# W707F.net
KiCad netlist of a schematic drawn in EAGLE
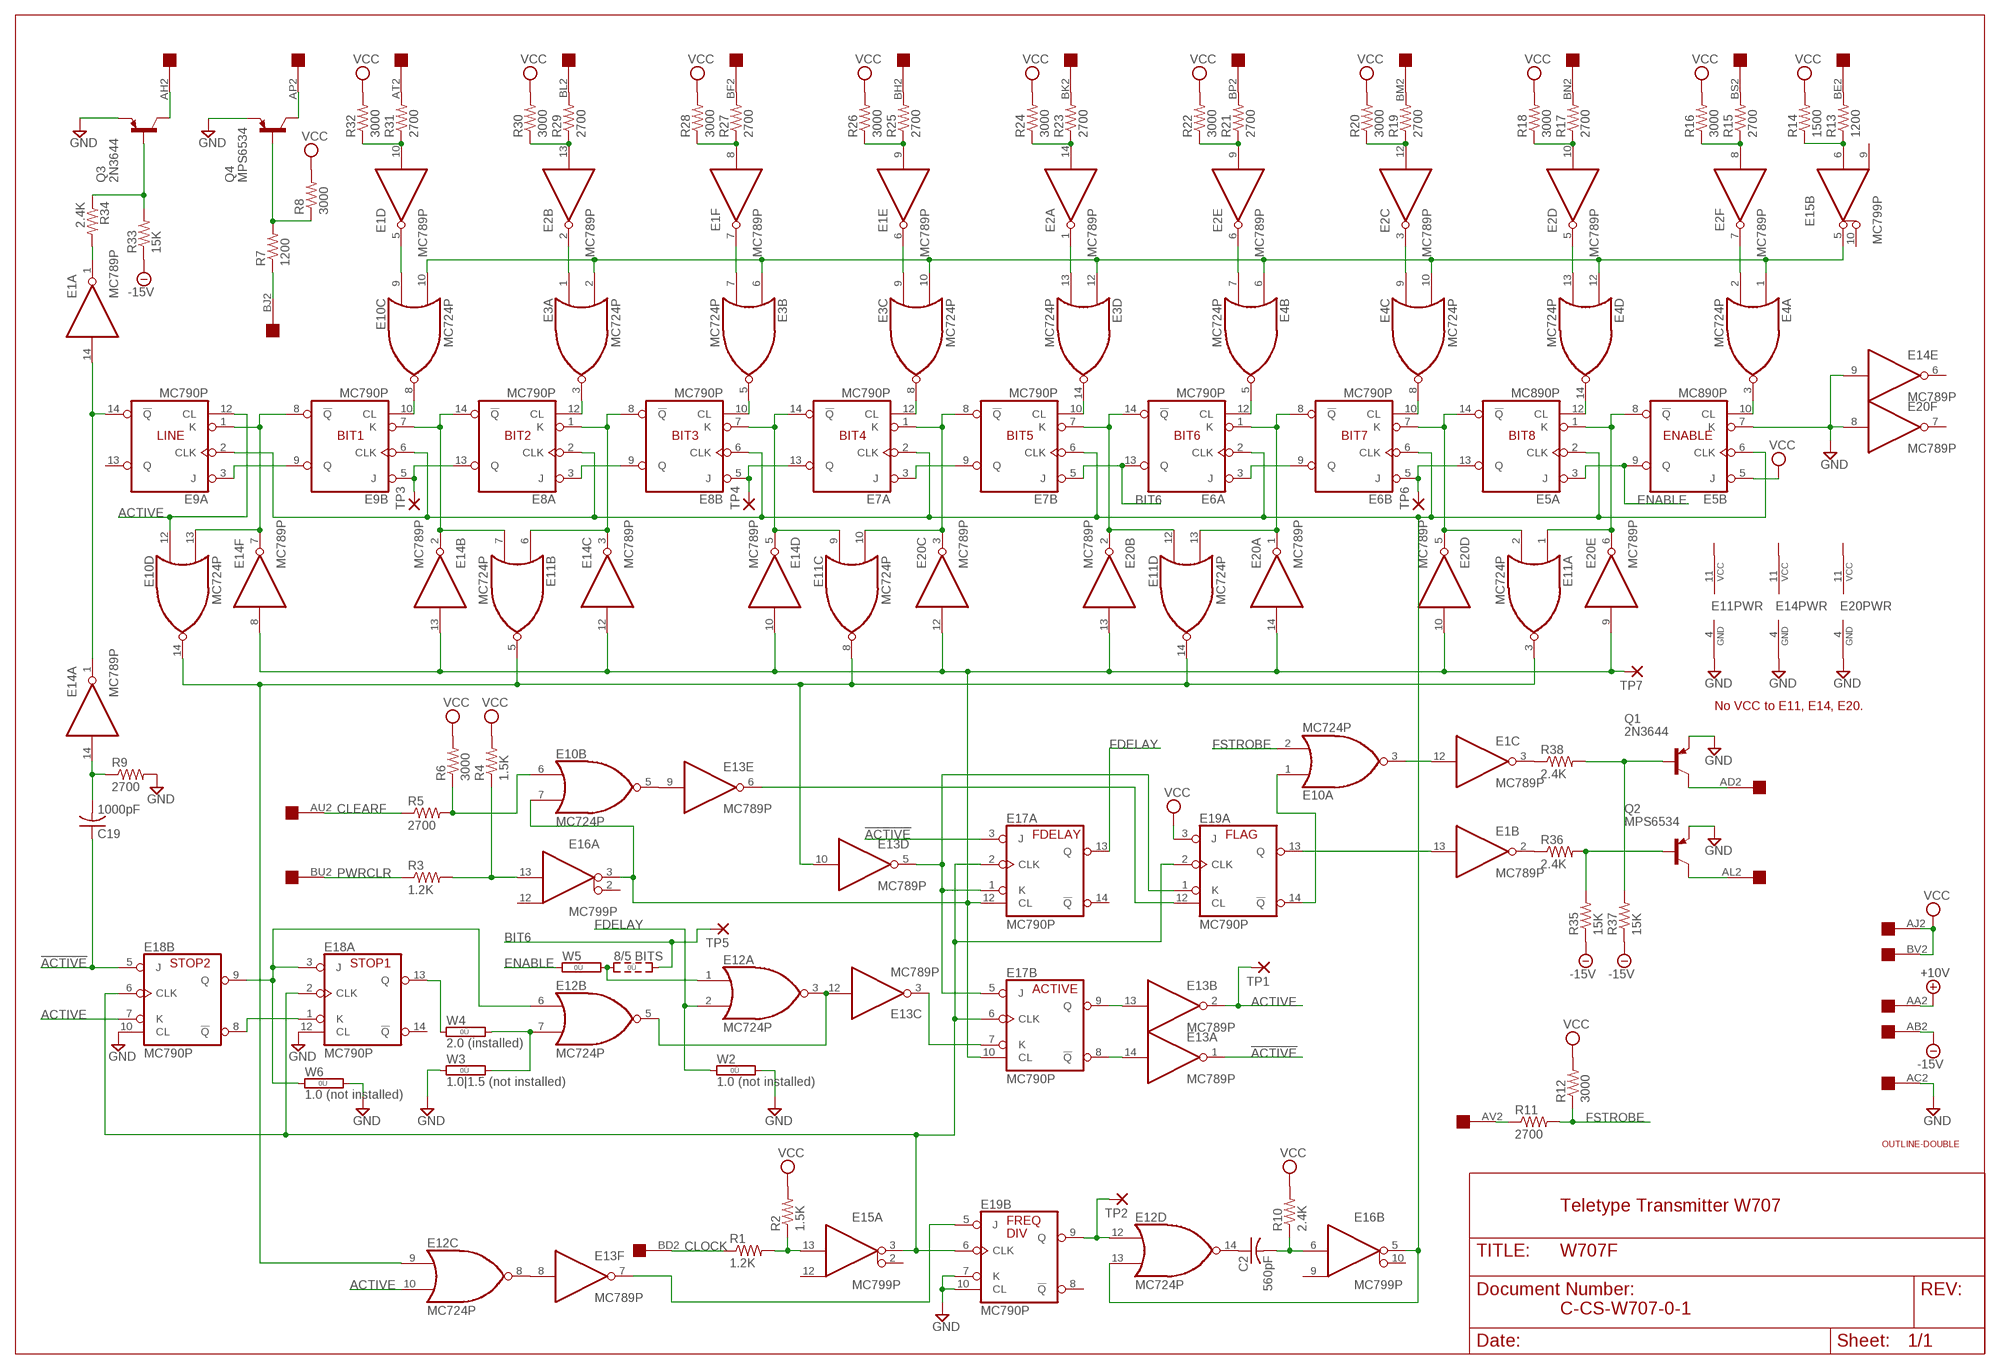
[diagram p0: schematic, sheet 1]

(export (version "E")
  (design (tool "Eeschema 10.0.6"))
  (components
    (comp (ref "C2")
      (value "560pF")
      (footprint "eagle-import:C050-025X075")
      (libsource (lib "eagle-import") (part "C-US050-025X075"))
    )
    (comp (ref "C19")
      (value "1000pF")
      (footprint "eagle-import:C050-025X075")
      (libsource (lib "eagle-import") (part "C-US050-025X075"))
    )
    (comp (ref "E1")
      (value "MC789P")
      (footprint "eagle-import:DIL14")
      (libsource (lib "eagle-import") (part "MC889P"))
    )
    (comp (ref "E2")
      (value "MC789P")
      (footprint "eagle-import:DIL14")
      (libsource (lib "eagle-import") (part "MC889P"))
    )
    (comp (ref "E3")
      (value "MC724P")
      (footprint "eagle-import:DIL14")
      (libsource (lib "eagle-import") (part "MC824P"))
    )
    (comp (ref "E4")
      (value "MC724P")
      (footprint "eagle-import:DIL14")
      (libsource (lib "eagle-import") (part "MC824P"))
    )
    (comp (ref "E5")
      (value "MC890P")
      (footprint "eagle-import:DIL14")
      (libsource (lib "eagle-import") (part "MC890P"))
    )
    (comp (ref "E6")
      (value "MC790P")
      (footprint "eagle-import:DIL14")
      (libsource (lib "eagle-import") (part "MC890P"))
    )
    (comp (ref "E7")
      (value "MC790P")
      (footprint "eagle-import:DIL14")
      (libsource (lib "eagle-import") (part "MC890P"))
    )
    (comp (ref "E8")
      (value "MC790P")
      (footprint "eagle-import:DIL14")
      (libsource (lib "eagle-import") (part "MC890P"))
    )
    (comp (ref "E9")
      (value "MC790P")
      (footprint "eagle-import:DIL14")
      (libsource (lib "eagle-import") (part "MC890P"))
    )
    (comp (ref "E10")
      (value "MC724P")
      (footprint "eagle-import:DIL14")
      (libsource (lib "eagle-import") (part "MC824P"))
    )
    (comp (ref "E11")
      (value "MC724P")
      (footprint "eagle-import:DIL14")
      (libsource (lib "eagle-import") (part "MC824P"))
    )
    (comp (ref "E12")
      (value "MC724P")
      (footprint "eagle-import:DIL14")
      (libsource (lib "eagle-import") (part "MC824P"))
    )
    (comp (ref "E13")
      (value "MC789P")
      (footprint "eagle-import:DIL14")
      (libsource (lib "eagle-import") (part "MC889P"))
    )
    (comp (ref "E14")
      (value "MC789P")
      (footprint "eagle-import:DIL14")
      (libsource (lib "eagle-import") (part "MC889P"))
    )
    (comp (ref "E15")
      (value "MC799P")
      (footprint "eagle-import:DIL14")
      (libsource (lib "eagle-import") (part "MC899P"))
    )
    (comp (ref "E16")
      (value "MC799P")
      (footprint "eagle-import:DIL14")
      (libsource (lib "eagle-import") (part "MC899P"))
    )
    (comp (ref "E17")
      (value "MC790P")
      (footprint "eagle-import:DIL14")
      (libsource (lib "eagle-import") (part "MC890P"))
    )
    (comp (ref "E18")
      (value "MC790P")
      (footprint "eagle-import:DIL14")
      (libsource (lib "eagle-import") (part "MC890P"))
    )
    (comp (ref "E19")
      (value "MC790P")
      (footprint "eagle-import:DIL14")
      (libsource (lib "eagle-import") (part "MC890P"))
    )
    (comp (ref "E20")
      (value "MC789P")
      (footprint "eagle-import:DIL14")
      (libsource (lib "eagle-import") (part "MC889P"))
    )
    (comp (ref "Q1")
      (value "2N3644")
      (footprint "eagle-import:TO39")
      (libsource (lib "eagle-import") (part "2N2904"))
    )
    (comp (ref "Q2")
      (value "MPS6534")
      (footprint "eagle-import:TO39")
      (libsource (lib "eagle-import") (part "2N2904"))
    )
    (comp (ref "Q3")
      (value "2N3644")
      (footprint "eagle-import:TO39")
      (libsource (lib "eagle-import") (part "2N2904"))
    )
    (comp (ref "Q4")
      (value "MPS6534")
      (footprint "eagle-import:TO39")
      (libsource (lib "eagle-import") (part "2N2904"))
    )
    (comp (ref "R1")
      (value "1.2K")
      (footprint "eagle-import:0207_10")
      (libsource (lib "eagle-import") (part "R-US_0207/10"))
    )
    (comp (ref "R2")
      (value "1.5K")
      (footprint "eagle-import:0207_10")
      (libsource (lib "eagle-import") (part "R-US_0207/10"))
    )
    (comp (ref "R3")
      (value "1.2K")
      (footprint "eagle-import:0207_10")
      (libsource (lib "eagle-import") (part "R-US_0207/10"))
    )
    (comp (ref "R4")
      (value "1.5K")
      (footprint "eagle-import:0207_10")
      (libsource (lib "eagle-import") (part "R-US_0207/10"))
    )
    (comp (ref "R5")
      (value "2700")
      (footprint "eagle-import:0207_10")
      (libsource (lib "eagle-import") (part "R-US_0207/10"))
    )
    (comp (ref "R6")
      (value "3000")
      (footprint "eagle-import:0207_10")
      (libsource (lib "eagle-import") (part "R-US_0207/10"))
    )
    (comp (ref "R7")
      (value "1200")
      (footprint "eagle-import:0207_10")
      (libsource (lib "eagle-import") (part "R-US_0207/10"))
    )
    (comp (ref "R8")
      (value "3000")
      (footprint "eagle-import:0207_10")
      (libsource (lib "eagle-import") (part "R-US_0207/10"))
    )
    (comp (ref "R9")
      (value "2700")
      (footprint "eagle-import:0207_10")
      (libsource (lib "eagle-import") (part "R-US_0207/10"))
    )
    (comp (ref "R10")
      (value "2.4K")
      (footprint "eagle-import:0207_10")
      (libsource (lib "eagle-import") (part "R-US_0207/10"))
    )
    (comp (ref "R11")
      (value "2700")
      (footprint "eagle-import:0207_10")
      (libsource (lib "eagle-import") (part "R-US_0207/10"))
    )
    (comp (ref "R12")
      (value "3000")
      (footprint "eagle-import:0207_10")
      (libsource (lib "eagle-import") (part "R-US_0207/10"))
    )
    (comp (ref "R13")
      (value "1200")
      (footprint "eagle-import:0207_10")
      (libsource (lib "eagle-import") (part "R-US_0207/10"))
    )
    (comp (ref "R14")
      (value "1500")
      (footprint "eagle-import:0207_10")
      (libsource (lib "eagle-import") (part "R-US_0207/10"))
    )
    (comp (ref "R15")
      (value "2700")
      (footprint "eagle-import:0207_10")
      (libsource (lib "eagle-import") (part "R-US_0207/10"))
    )
    (comp (ref "R16")
      (value "3000")
      (footprint "eagle-import:0207_10")
      (libsource (lib "eagle-import") (part "R-US_0207/10"))
    )
    (comp (ref "R17")
      (value "2700")
      (footprint "eagle-import:0207_10")
      (libsource (lib "eagle-import") (part "R-US_0207/10"))
    )
    (comp (ref "R18")
      (value "3000")
      (footprint "eagle-import:0207_10")
      (libsource (lib "eagle-import") (part "R-US_0207/10"))
    )
    (comp (ref "R19")
      (value "2700")
      (footprint "eagle-import:0207_10")
      (libsource (lib "eagle-import") (part "R-US_0207/10"))
    )
    (comp (ref "R20")
      (value "3000")
      (footprint "eagle-import:0207_10")
      (libsource (lib "eagle-import") (part "R-US_0207/10"))
    )
    (comp (ref "R21")
      (value "2700")
      (footprint "eagle-import:0207_10")
      (libsource (lib "eagle-import") (part "R-US_0207/10"))
    )
    (comp (ref "R22")
      (value "3000")
      (footprint "eagle-import:0207_10")
      (libsource (lib "eagle-import") (part "R-US_0207/10"))
    )
    (comp (ref "R23")
      (value "2700")
      (footprint "eagle-import:0207_10")
      (libsource (lib "eagle-import") (part "R-US_0207/10"))
    )
    (comp (ref "R24")
      (value "3000")
      (footprint "eagle-import:0207_10")
      (libsource (lib "eagle-import") (part "R-US_0207/10"))
    )
    (comp (ref "R25")
      (value "2700")
      (footprint "eagle-import:0207_10")
      (libsource (lib "eagle-import") (part "R-US_0207/10"))
    )
    (comp (ref "R26")
      (value "3000")
      (footprint "eagle-import:0207_10")
      (libsource (lib "eagle-import") (part "R-US_0207/10"))
    )
    (comp (ref "R27")
      (value "2700")
      (footprint "eagle-import:0207_10")
      (libsource (lib "eagle-import") (part "R-US_0207/10"))
    )
    (comp (ref "R28")
      (value "3000")
      (footprint "eagle-import:0207_10")
      (libsource (lib "eagle-import") (part "R-US_0207/10"))
    )
    (comp (ref "R29")
      (value "2700")
      (footprint "eagle-import:0207_10")
      (libsource (lib "eagle-import") (part "R-US_0207/10"))
    )
    (comp (ref "R30")
      (value "3000")
      (footprint "eagle-import:0207_10")
      (libsource (lib "eagle-import") (part "R-US_0207/10"))
    )
    (comp (ref "R31")
      (value "2700")
      (footprint "eagle-import:0207_10")
      (libsource (lib "eagle-import") (part "R-US_0207/10"))
    )
    (comp (ref "R32")
      (value "3000")
      (footprint "eagle-import:0207_10")
      (libsource (lib "eagle-import") (part "R-US_0207/10"))
    )
    (comp (ref "R33")
      (value "15K")
      (footprint "eagle-import:0207_10")
      (libsource (lib "eagle-import") (part "R-US_0207/10"))
    )
    (comp (ref "R34")
      (value "2.4K")
      (footprint "eagle-import:0207_10")
      (libsource (lib "eagle-import") (part "R-US_0207/10"))
    )
    (comp (ref "R35")
      (value "15K")
      (footprint "eagle-import:0207_10")
      (libsource (lib "eagle-import") (part "R-US_0207/10"))
    )
    (comp (ref "R36")
      (value "2.4K")
      (footprint "eagle-import:0207_10")
      (libsource (lib "eagle-import") (part "R-US_0207/10"))
    )
    (comp (ref "R37")
      (value "15K")
      (footprint "eagle-import:0207_10")
      (libsource (lib "eagle-import") (part "R-US_0207/10"))
    )
    (comp (ref "R38")
      (value "2.4K")
      (footprint "eagle-import:0207_10")
      (libsource (lib "eagle-import") (part "R-US_0207/10"))
    )
    (comp (ref "TP1")
      (value "3,17/1,3")
      (footprint "eagle-import:3,17_1,3")
      (libsource (lib "eagle-import") (part "3,17/1,3"))
    )
    (comp (ref "TP2")
      (value "3,17/1,3")
      (footprint "eagle-import:3,17_1,3")
      (libsource (lib "eagle-import") (part "3,17/1,3"))
    )
    (comp (ref "TP3")
      (value "3,17/1,3")
      (footprint "eagle-import:3,17_1,3")
      (libsource (lib "eagle-import") (part "3,17/1,3"))
    )
    (comp (ref "TP4")
      (value "3,17/1,3")
      (footprint "eagle-import:3,17_1,3")
      (libsource (lib "eagle-import") (part "3,17/1,3"))
    )
    (comp (ref "TP5")
      (value "3,17/1,3")
      (footprint "eagle-import:3,17_1,3")
      (libsource (lib "eagle-import") (part "3,17/1,3"))
    )
    (comp (ref "TP6")
      (value "3,17/1,3")
      (footprint "eagle-import:3,17_1,3")
      (libsource (lib "eagle-import") (part "3,17/1,3"))
    )
    (comp (ref "TP7")
      (value "3,17/1,3")
      (footprint "eagle-import:3,17_1,3")
      (libsource (lib "eagle-import") (part "3,17/1,3"))
    )
    (comp (ref "U$1")
      (value "OUTLINE-DOUBLE")
      (footprint "eagle-import:DOUBLE")
      (libsource (lib "eagle-import") (part "OUTLINE-DOUBLE"))
    )
    (comp (ref "U$2")
      (value "DOUBLE")
      (footprint "eagle-import:EDGE-CON4")
      (libsource (lib "eagle-import") (part "DOUBLE"))
    )
    (comp (ref "W2")
      (value "1.0 (not installed)")
      (footprint "eagle-import:0R_10")
      (libsource (lib "eagle-import") (part "0R"))
    )
    (comp (ref "W3")
      (value "1.0|1.5 (not installed)")
      (footprint "eagle-import:0R_10")
      (libsource (lib "eagle-import") (part "0R"))
    )
    (comp (ref "W4")
      (value "2.0 (installed)")
      (footprint "eagle-import:0R_10")
      (libsource (lib "eagle-import") (part "0R"))
    )
    (comp (ref "W5")
      (value "8/5 BITS")
      (footprint "eagle-import:0R2_10")
      (libsource (lib "eagle-import") (part "0R2"))
    )
    (comp (ref "W6")
      (value "1.0 (not installed)")
      (footprint "eagle-import:0R_10")
      (libsource (lib "eagle-import") (part "0R"))
    )
  )
  (nets
    (net (code "1") (name "+10V") (class "Default")
      (node (ref "U$2") (pin "AA2") (pinfunction "1_AA2") (pintype "bidirectional"))
    )
    (net (code "2") (name "-15V") (class "Default")
      (node (ref "R33") (pin "1") (pinfunction "1_1") (pintype "passive"))
      (node (ref "R35") (pin "1") (pinfunction "1_1") (pintype "passive"))
      (node (ref "R37") (pin "1") (pinfunction "1_1") (pintype "passive"))
      (node (ref "U$2") (pin "AB2") (pinfunction "1_AB2") (pintype "bidirectional"))
    )
    (net (code "3") (name "/ACTIVE") (class "Default")
      (node (ref "E10") (pin "12") (pinfunction "I0_12") (pintype "input"))
      (node (ref "E12") (pin "10") (pinfunction "I1_10") (pintype "input"))
      (node (ref "E13") (pin "2") (pinfunction "O_2") (pintype "output"))
      (node (ref "E18") (pin "7") (pinfunction "K_7") (pintype "input"))
      (node (ref "E9") (pin "12") (pinfunction "CL_12") (pintype "input"))
      (node (ref "TP1") (pin "1") (pinfunction "P_1") (pintype "passive"))
    )
    (net (code "4") (name "/BIT6") (class "Default")
      (node (ref "E6") (pin "13") (pinfunction "Q_13") (pintype "output"))
      (node (ref "E7") (pin "5") (pinfunction "J_5") (pintype "input"))
      (node (ref "TP5") (pin "1") (pinfunction "P_1") (pintype "passive"))
      (node (ref "W5") (pin "3") (pinfunction "3_3") (pintype "passive"))
    )
    (net (code "5") (name "/CLEARF") (class "Default")
      (node (ref "R5") (pin "1") (pinfunction "1_1") (pintype "passive"))
      (node (ref "U$2") (pin "AU2") (pinfunction "1_AU2") (pintype "bidirectional"))
    )
    (net (code "6") (name "/CLOCK") (class "Default")
      (node (ref "R1") (pin "1") (pinfunction "1_1") (pintype "passive"))
      (node (ref "U$2") (pin "BD2") (pinfunction "1_BD2") (pintype "bidirectional"))
    )
    (net (code "7") (name "/ENABLE") (class "Default")
      (node (ref "E5") (pin "3") (pinfunction "J_3") (pintype "input"))
      (node (ref "E5") (pin "9") (pinfunction "Q_9") (pintype "output"))
      (node (ref "W5") (pin "1") (pinfunction "1_1") (pintype "passive"))
    )
    (net (code "8") (name "/FDELAY") (class "Default")
      (node (ref "E12") (pin "2") (pinfunction "I1_2") (pintype "input"))
      (node (ref "E17") (pin "13") (pinfunction "Q_13") (pintype "output"))
      (node (ref "W2") (pin "1") (pinfunction "1_1") (pintype "passive"))
    )
    (net (code "9") (name "/FSTROBE") (class "Default")
      (node (ref "E10") (pin "2") (pinfunction "I1_2") (pintype "input"))
      (node (ref "R11") (pin "2") (pinfunction "2_2") (pintype "passive"))
      (node (ref "R12") (pin "1") (pinfunction "1_1") (pintype "passive"))
    )
    (net (code "10") (name "/PWRCLR") (class "Default")
      (node (ref "R3") (pin "1") (pinfunction "1_1") (pintype "passive"))
      (node (ref "U$2") (pin "BU2") (pinfunction "1_BU2") (pintype "bidirectional"))
    )
    (net (code "11") (name "/~{ACTIVE}") (class "Default")
      (node (ref "C19") (pin "1") (pinfunction "1_1") (pintype "passive"))
      (node (ref "E13") (pin "1") (pinfunction "O_1") (pintype "output"))
      (node (ref "E17") (pin "3") (pinfunction "J_3") (pintype "input"))
      (node (ref "E18") (pin "5") (pinfunction "J_5") (pintype "input"))
    )
    (net (code "12") (name "GND") (class "Default")
      (node (ref "E11") (pin "4") (pinfunction "GND_4") (pintype "power_in"))
      (node (ref "E14") (pin "4") (pinfunction "GND_4") (pintype "power_in"))
      (node (ref "E14") (pin "9") (pinfunction "I_9") (pintype "input"))
      (node (ref "E18") (pin "10") (pinfunction "CL_10") (pintype "input"))
      (node (ref "E18") (pin "12") (pinfunction "CL_12") (pintype "input"))
      (node (ref "E19") (pin "10") (pinfunction "CL_10") (pintype "input"))
      (node (ref "E19") (pin "7") (pinfunction "K_7") (pintype "input"))
      (node (ref "E20") (pin "4") (pinfunction "GND_4") (pintype "power_in"))
      (node (ref "E20") (pin "8") (pinfunction "I_8") (pintype "input"))
      (node (ref "E5") (pin "7") (pinfunction "K_7") (pintype "input"))
      (node (ref "Q1") (pin "1") (pinfunction "E_1") (pintype "passive"))
      (node (ref "Q2") (pin "1") (pinfunction "E_1") (pintype "passive"))
      (node (ref "Q3") (pin "1") (pinfunction "E_1") (pintype "passive"))
      (node (ref "Q4") (pin "1") (pinfunction "E_1") (pintype "passive"))
      (node (ref "R9") (pin "2") (pinfunction "2_2") (pintype "passive"))
      (node (ref "U$2") (pin "AC2") (pinfunction "1_AC2") (pintype "bidirectional"))
      (node (ref "W2") (pin "2") (pinfunction "2_2") (pintype "passive"))
      (node (ref "W3") (pin "1") (pinfunction "1_1") (pintype "passive"))
      (node (ref "W6") (pin "2") (pinfunction "2_2") (pintype "passive"))
    )
    (net (code "13") (name "NC") (class "Default")
      (node (ref "E11") (pin "11") (pinfunction "VCC_11") (pintype "power_in"))
      (node (ref "E14") (pin "11") (pinfunction "VCC_11") (pintype "power_in"))
      (node (ref "E20") (pin "11") (pinfunction "VCC_11") (pintype "power_in"))
    )
    (net (code "14") (name "Net-(E1A-O)") (class "Default")
      (node (ref "E1") (pin "1") (pinfunction "O_1") (pintype "output"))
      (node (ref "R34") (pin "2") (pinfunction "2_2") (pintype "passive"))
    )
    (net (code "15") (name "Net-(E1B-O)") (class "Default")
      (node (ref "E1") (pin "2") (pinfunction "O_2") (pintype "output"))
      (node (ref "R36") (pin "1") (pinfunction "1_1") (pintype "passive"))
    )
    (net (code "16") (name "Net-(E1C-O)") (class "Default")
      (node (ref "E1") (pin "3") (pinfunction "O_3") (pintype "output"))
      (node (ref "R38") (pin "1") (pinfunction "1_1") (pintype "passive"))
    )
    (net (code "17") (name "Net-(E1D-I)") (class "Default")
      (node (ref "E1") (pin "10") (pinfunction "I_10") (pintype "input"))
      (node (ref "R31") (pin "1") (pinfunction "1_1") (pintype "passive"))
      (node (ref "R32") (pin "1") (pinfunction "1_1") (pintype "passive"))
    )
    (net (code "18") (name "Net-(E1E-I)") (class "Default")
      (node (ref "E1") (pin "9") (pinfunction "I_9") (pintype "input"))
      (node (ref "R25") (pin "1") (pinfunction "1_1") (pintype "passive"))
      (node (ref "R26") (pin "1") (pinfunction "1_1") (pintype "passive"))
    )
    (net (code "19") (name "Net-(E1E-O)") (class "Default")
      (node (ref "E1") (pin "6") (pinfunction "O_6") (pintype "output"))
      (node (ref "E3") (pin "9") (pinfunction "I0_9") (pintype "input"))
    )
    (net (code "20") (name "Net-(E1F-I)") (class "Default")
      (node (ref "E1") (pin "8") (pinfunction "I_8") (pintype "input"))
      (node (ref "R27") (pin "1") (pinfunction "1_1") (pintype "passive"))
      (node (ref "R28") (pin "1") (pinfunction "1_1") (pintype "passive"))
    )
    (net (code "21") (name "Net-(E1F-O)") (class "Default")
      (node (ref "E1") (pin "7") (pinfunction "O_7") (pintype "output"))
      (node (ref "E3") (pin "7") (pinfunction "I1_7") (pintype "input"))
    )
    (net (code "22") (name "Net-(E2A-I)") (class "Default")
      (node (ref "E2") (pin "14") (pinfunction "I_14") (pintype "input"))
      (node (ref "R23") (pin "1") (pinfunction "1_1") (pintype "passive"))
      (node (ref "R24") (pin "1") (pinfunction "1_1") (pintype "passive"))
    )
    (net (code "23") (name "Net-(E2A-O)") (class "Default")
      (node (ref "E2") (pin "1") (pinfunction "O_1") (pintype "output"))
      (node (ref "E3") (pin "13") (pinfunction "I1_13") (pintype "input"))
    )
    (net (code "24") (name "Net-(E2B-I)") (class "Default")
      (node (ref "E2") (pin "13") (pinfunction "I_13") (pintype "input"))
      (node (ref "R29") (pin "1") (pinfunction "1_1") (pintype "passive"))
      (node (ref "R30") (pin "1") (pinfunction "1_1") (pintype "passive"))
    )
    (net (code "25") (name "Net-(E2B-O)") (class "Default")
      (node (ref "E2") (pin "2") (pinfunction "O_2") (pintype "output"))
      (node (ref "E3") (pin "1") (pinfunction "I0_1") (pintype "input"))
    )
    (net (code "26") (name "Net-(E2C-I)") (class "Default")
      (node (ref "E2") (pin "12") (pinfunction "I_12") (pintype "input"))
      (node (ref "R19") (pin "1") (pinfunction "1_1") (pintype "passive"))
      (node (ref "R20") (pin "1") (pinfunction "1_1") (pintype "passive"))
    )
    (net (code "27") (name "Net-(E2C-O)") (class "Default")
      (node (ref "E2") (pin "3") (pinfunction "O_3") (pintype "output"))
      (node (ref "E4") (pin "9") (pinfunction "I0_9") (pintype "input"))
    )
    (net (code "28") (name "Net-(E2D-I)") (class "Default")
      (node (ref "E2") (pin "10") (pinfunction "I_10") (pintype "input"))
      (node (ref "R17") (pin "1") (pinfunction "1_1") (pintype "passive"))
      (node (ref "R18") (pin "1") (pinfunction "1_1") (pintype "passive"))
    )
    (net (code "29") (name "Net-(E2D-O)") (class "Default")
      (node (ref "E2") (pin "5") (pinfunction "O_5") (pintype "output"))
      (node (ref "E4") (pin "13") (pinfunction "I1_13") (pintype "input"))
    )
    (net (code "30") (name "Net-(E2E-I)") (class "Default")
      (node (ref "E2") (pin "9") (pinfunction "I_9") (pintype "input"))
      (node (ref "R21") (pin "1") (pinfunction "1_1") (pintype "passive"))
      (node (ref "R22") (pin "1") (pinfunction "1_1") (pintype "passive"))
    )
    (net (code "31") (name "Net-(E2E-O)") (class "Default")
      (node (ref "E2") (pin "6") (pinfunction "O_6") (pintype "output"))
      (node (ref "E4") (pin "7") (pinfunction "I1_7") (pintype "input"))
    )
    (net (code "32") (name "Net-(E2F-I)") (class "Default")
      (node (ref "E2") (pin "8") (pinfunction "I_8") (pintype "input"))
      (node (ref "R15") (pin "1") (pinfunction "1_1") (pintype "passive"))
      (node (ref "R16") (pin "1") (pinfunction "1_1") (pintype "passive"))
    )
    (net (code "33") (name "Net-(E2F-O)") (class "Default")
      (node (ref "E2") (pin "7") (pinfunction "O_7") (pintype "output"))
      (node (ref "E4") (pin "2") (pinfunction "I1_2") (pintype "input"))
    )
    (net (code "34") (name "Net-(E3A-O)") (class "Default")
      (node (ref "E3") (pin "3") (pinfunction "O_3") (pintype "output"))
      (node (ref "E8") (pin "12") (pinfunction "CL_12") (pintype "input"))
    )
    (net (code "35") (name "Net-(E3B-O)") (class "Default")
      (node (ref "E3") (pin "5") (pinfunction "O_5") (pintype "output"))
      (node (ref "E8") (pin "10") (pinfunction "CL_10") (pintype "input"))
    )
    (net (code "36") (name "Net-(E3C-O)") (class "Default")
      (node (ref "E3") (pin "8") (pinfunction "O_8") (pintype "output"))
      (node (ref "E7") (pin "12") (pinfunction "CL_12") (pintype "input"))
    )
    (net (code "37") (name "Net-(E3D-O)") (class "Default")
      (node (ref "E3") (pin "14") (pinfunction "O_14") (pintype "output"))
      (node (ref "E7") (pin "10") (pinfunction "CL_10") (pintype "input"))
    )
    (net (code "38") (name "Net-(E4A-O)") (class "Default")
      (node (ref "E4") (pin "3") (pinfunction "O_3") (pintype "output"))
      (node (ref "E5") (pin "10") (pinfunction "CL_10") (pintype "input"))
    )
    (net (code "39") (name "Net-(E4B-O)") (class "Default")
      (node (ref "E4") (pin "5") (pinfunction "O_5") (pintype "output"))
      (node (ref "E6") (pin "12") (pinfunction "CL_12") (pintype "input"))
    )
    (net (code "40") (name "Net-(E4C-O)") (class "Default")
      (node (ref "E4") (pin "8") (pinfunction "O_8") (pintype "output"))
      (node (ref "E6") (pin "10") (pinfunction "CL_10") (pintype "input"))
    )
    (net (code "41") (name "Net-(E4D-O)") (class "Default")
      (node (ref "E4") (pin "14") (pinfunction "O_14") (pintype "output"))
      (node (ref "E5") (pin "12") (pinfunction "CL_12") (pintype "input"))
    )
    (net (code "42") (name "Net-(E5A-Q)") (class "Default")
      (node (ref "E5") (pin "13") (pinfunction "Q_13") (pintype "output"))
      (node (ref "E6") (pin "5") (pinfunction "J_5") (pintype "input"))
      (node (ref "TP6") (pin "1") (pinfunction "P_1") (pintype "passive"))
    )
    (net (code "43") (name "Net-(E6A-J)") (class "Default")
      (node (ref "E6") (pin "3") (pinfunction "J_3") (pintype "input"))
      (node (ref "E6") (pin "9") (pinfunction "Q_9") (pintype "output"))
    )
    (net (code "44") (name "Net-(E7A-J)") (class "Default")
      (node (ref "E7") (pin "3") (pinfunction "J_3") (pintype "input"))
      (node (ref "E7") (pin "9") (pinfunction "Q_9") (pintype "output"))
    )
    (net (code "45") (name "Net-(E7A-Q)") (class "Default")
      (node (ref "E7") (pin "13") (pinfunction "Q_13") (pintype "output"))
      (node (ref "E8") (pin "5") (pinfunction "J_5") (pintype "input"))
      (node (ref "TP4") (pin "1") (pinfunction "P_1") (pintype "passive"))
    )
    (net (code "46") (name "Net-(E8A-J)") (class "Default")
      (node (ref "E8") (pin "3") (pinfunction "J_3") (pintype "input"))
      (node (ref "E8") (pin "9") (pinfunction "Q_9") (pintype "output"))
    )
    (net (code "47") (name "Net-(E8A-Q)") (class "Default")
      (node (ref "E8") (pin "13") (pinfunction "Q_13") (pintype "output"))
      (node (ref "E9") (pin "5") (pinfunction "J_5") (pintype "input"))
      (node (ref "TP3") (pin "1") (pinfunction "P_1") (pintype "passive"))
    )
    (net (code "48") (name "Net-(E9A-J)") (class "Default")
      (node (ref "E9") (pin "3") (pinfunction "J_3") (pintype "input"))
      (node (ref "E9") (pin "9") (pinfunction "Q_9") (pintype "output"))
    )
    (net (code "49") (name "Net-(E10A-I0)") (class "Default")
      (node (ref "E10") (pin "1") (pinfunction "I0_1") (pintype "input"))
      (node (ref "E19") (pin "14") (pinfunction "~{Q}_14") (pintype "output"))
    )
    (net (code "50") (name "Net-(E10A-O)") (class "Default")
      (node (ref "E1") (pin "12") (pinfunction "I_12") (pintype "input"))
      (node (ref "E10") (pin "3") (pinfunction "O_3") (pintype "output"))
    )
    (net (code "51") (name "Net-(E10B-I0)") (class "Default")
      (node (ref "E10") (pin "6") (pinfunction "I0_6") (pintype "input"))
      (node (ref "R5") (pin "2") (pinfunction "2_2") (pintype "passive"))
      (node (ref "R6") (pin "1") (pinfunction "1_1") (pintype "passive"))
    )
    (net (code "52") (name "Net-(E10B-I1)") (class "Default")
      (node (ref "E10") (pin "7") (pinfunction "I1_7") (pintype "input"))
      (node (ref "E14") (pin "10") (pinfunction "I_10") (pintype "input"))
      (node (ref "E14") (pin "12") (pinfunction "I_12") (pintype "input"))
      (node (ref "E14") (pin "13") (pinfunction "I_13") (pintype "input"))
      (node (ref "E14") (pin "8") (pinfunction "I_8") (pintype "input"))
      (node (ref "E16") (pin "3") (pinfunction "O_3") (pintype "output"))
      (node (ref "E17") (pin "10") (pinfunction "CL_10") (pintype "input"))
      (node (ref "E17") (pin "12") (pinfunction "CL_12") (pintype "input"))
      (node (ref "E20") (pin "10") (pinfunction "I_10") (pintype "input"))
      (node (ref "E20") (pin "12") (pinfunction "I_12") (pintype "input"))
      (node (ref "E20") (pin "13") (pinfunction "I_13") (pintype "input"))
      (node (ref "E20") (pin "14") (pinfunction "I_14") (pintype "input"))
      (node (ref "E20") (pin "9") (pinfunction "I_9") (pintype "input"))
      (node (ref "TP7") (pin "1") (pinfunction "P_1") (pintype "passive"))
    )
    (net (code "53") (name "Net-(E10B-O)") (class "Default")
      (node (ref "E10") (pin "5") (pinfunction "O_5") (pintype "output"))
      (node (ref "E13") (pin "9") (pinfunction "I_9") (pintype "input"))
    )
    (net (code "54") (name "Net-(E10C-I0)") (class "Default")
      (node (ref "E1") (pin "5") (pinfunction "O_5") (pintype "output"))
      (node (ref "E10") (pin "9") (pinfunction "I0_9") (pintype "input"))
    )
    (net (code "55") (name "Net-(E10C-I1)") (class "Default")
      (node (ref "E10") (pin "10") (pinfunction "I1_10") (pintype "input"))
      (node (ref "E15") (pin "5") (pinfunction "O_5") (pintype "output"))
      (node (ref "E3") (pin "10") (pinfunction "I1_10") (pintype "input"))
      (node (ref "E3") (pin "12") (pinfunction "I0_12") (pintype "input"))
      (node (ref "E3") (pin "2") (pinfunction "I1_2") (pintype "input"))
      (node (ref "E3") (pin "6") (pinfunction "I0_6") (pintype "input"))
      (node (ref "E4") (pin "1") (pinfunction "I0_1") (pintype "input"))
      (node (ref "E4") (pin "10") (pinfunction "I1_10") (pintype "input"))
      (node (ref "E4") (pin "12") (pinfunction "I0_12") (pintype "input"))
      (node (ref "E4") (pin "6") (pinfunction "I0_6") (pintype "input"))
    )
    (net (code "56") (name "Net-(E10C-O)") (class "Default")
      (node (ref "E10") (pin "8") (pinfunction "O_8") (pintype "output"))
      (node (ref "E9") (pin "10") (pinfunction "CL_10") (pintype "input"))
    )
    (net (code "57") (name "Net-(E10D-I1)") (class "Default")
      (node (ref "E10") (pin "13") (pinfunction "I1_13") (pintype "input"))
      (node (ref "E14") (pin "7") (pinfunction "O_7") (pintype "output"))
      (node (ref "E9") (pin "1") (pinfunction "K_1") (pintype "input"))
      (node (ref "E9") (pin "8") (pinfunction "~{Q}_8") (pintype "output"))
    )
    (net (code "58") (name "Net-(E10D-O)") (class "Default")
      (node (ref "E10") (pin "14") (pinfunction "O_14") (pintype "output"))
      (node (ref "E11") (pin "14") (pinfunction "O_14") (pintype "output"))
      (node (ref "E11") (pin "3") (pinfunction "O_3") (pintype "output"))
      (node (ref "E11") (pin "5") (pinfunction "O_5") (pintype "output"))
      (node (ref "E11") (pin "8") (pinfunction "O_8") (pintype "output"))
      (node (ref "E12") (pin "9") (pinfunction "I0_9") (pintype "input"))
      (node (ref "E13") (pin "10") (pinfunction "I_10") (pintype "input"))
    )
    (net (code "59") (name "Net-(E11A-I0)") (class "Default")
      (node (ref "E11") (pin "1") (pinfunction "I0_1") (pintype "input"))
      (node (ref "E20") (pin "6") (pinfunction "O_6") (pintype "output"))
      (node (ref "E5") (pin "1") (pinfunction "K_1") (pintype "input"))
      (node (ref "E5") (pin "8") (pinfunction "~{Q}_8") (pintype "output"))
    )
    (net (code "60") (name "Net-(E11A-I1)") (class "Default")
      (node (ref "E11") (pin "2") (pinfunction "I1_2") (pintype "input"))
      (node (ref "E20") (pin "5") (pinfunction "O_5") (pintype "output"))
      (node (ref "E5") (pin "14") (pinfunction "~{Q}_14") (pintype "output"))
      (node (ref "E6") (pin "7") (pinfunction "K_7") (pintype "input"))
    )
    (net (code "61") (name "Net-(E11B-I0)") (class "Default")
      (node (ref "E11") (pin "6") (pinfunction "I0_6") (pintype "input"))
      (node (ref "E14") (pin "3") (pinfunction "O_3") (pintype "output"))
      (node (ref "E8") (pin "1") (pinfunction "K_1") (pintype "input"))
      (node (ref "E8") (pin "8") (pinfunction "~{Q}_8") (pintype "output"))
    )
    (net (code "62") (name "Net-(E11B-I1)") (class "Default")
      (node (ref "E11") (pin "7") (pinfunction "I1_7") (pintype "input"))
      (node (ref "E14") (pin "2") (pinfunction "O_2") (pintype "output"))
      (node (ref "E8") (pin "14") (pinfunction "~{Q}_14") (pintype "output"))
      (node (ref "E9") (pin "7") (pinfunction "K_7") (pintype "input"))
    )
    (net (code "63") (name "Net-(E11C-I0)") (class "Default")
      (node (ref "E11") (pin "9") (pinfunction "I0_9") (pintype "input"))
      (node (ref "E14") (pin "5") (pinfunction "O_5") (pintype "output"))
      (node (ref "E7") (pin "14") (pinfunction "~{Q}_14") (pintype "output"))
      (node (ref "E8") (pin "7") (pinfunction "K_7") (pintype "input"))
    )
    (net (code "64") (name "Net-(E11C-I1)") (class "Default")
      (node (ref "E11") (pin "10") (pinfunction "I1_10") (pintype "input"))
      (node (ref "E20") (pin "3") (pinfunction "O_3") (pintype "output"))
      (node (ref "E7") (pin "1") (pinfunction "K_1") (pintype "input"))
      (node (ref "E7") (pin "8") (pinfunction "~{Q}_8") (pintype "output"))
    )
    (net (code "65") (name "Net-(E11D-I0)") (class "Default")
      (node (ref "E11") (pin "12") (pinfunction "I0_12") (pintype "input"))
      (node (ref "E20") (pin "2") (pinfunction "O_2") (pintype "output"))
      (node (ref "E6") (pin "14") (pinfunction "~{Q}_14") (pintype "output"))
      (node (ref "E7") (pin "7") (pinfunction "K_7") (pintype "input"))
    )
    (net (code "66") (name "Net-(E11D-I1)") (class "Default")
      (node (ref "E11") (pin "13") (pinfunction "I1_13") (pintype "input"))
      (node (ref "E20") (pin "1") (pinfunction "O_1") (pintype "output"))
      (node (ref "E6") (pin "1") (pinfunction "K_1") (pintype "input"))
      (node (ref "E6") (pin "8") (pinfunction "~{Q}_8") (pintype "output"))
    )
    (net (code "67") (name "Net-(E12A-I0)") (class "Default")
      (node (ref "E12") (pin "1") (pinfunction "I0_1") (pintype "input"))
      (node (ref "W5") (pin "2") (pinfunction "2_2") (pintype "passive"))
    )
    (net (code "68") (name "Net-(E12A-O)") (class "Default")
      (node (ref "E12") (pin "3") (pinfunction "O_3") (pintype "output"))
      (node (ref "E12") (pin "5") (pinfunction "O_5") (pintype "output"))
      (node (ref "E13") (pin "12") (pinfunction "I_12") (pintype "input"))
    )
    (net (code "69") (name "Net-(E12B-I0)") (class "Default")
      (node (ref "E12") (pin "6") (pinfunction "I0_6") (pintype "input"))
      (node (ref "E18") (pin "3") (pinfunction "J_3") (pintype "input"))
      (node (ref "E18") (pin "9") (pinfunction "Q_9") (pintype "output"))
      (node (ref "W6") (pin "1") (pinfunction "1_1") (pintype "passive"))
    )
    (net (code "70") (name "Net-(E12B-I1)") (class "Default")
      (node (ref "E12") (pin "7") (pinfunction "I1_7") (pintype "input"))
      (node (ref "W3") (pin "2") (pinfunction "2_2") (pintype "passive"))
      (node (ref "W4") (pin "2") (pinfunction "2_2") (pintype "passive"))
    )
    (net (code "71") (name "Net-(E12C-O)") (class "Default")
      (node (ref "E12") (pin "8") (pinfunction "O_8") (pintype "output"))
      (node (ref "E13") (pin "8") (pinfunction "I_8") (pintype "input"))
    )
    (net (code "72") (name "Net-(E12D-I0)") (class "Default")
      (node (ref "E12") (pin "12") (pinfunction "I0_12") (pintype "input"))
      (node (ref "E19") (pin "9") (pinfunction "Q_9") (pintype "output"))
      (node (ref "TP2") (pin "1") (pinfunction "P_1") (pintype "passive"))
    )
    (net (code "73") (name "Net-(E12D-I1)") (class "Default")
      (node (ref "E12") (pin "13") (pinfunction "I1_13") (pintype "input"))
      (node (ref "E16") (pin "5") (pinfunction "O_5") (pintype "output"))
      (node (ref "E5") (pin "2") (pinfunction "CLK_2") (pintype "input"))
      (node (ref "E5") (pin "6") (pinfunction "CLK_6") (pintype "input"))
      (node (ref "E6") (pin "2") (pinfunction "CLK_2") (pintype "input"))
      (node (ref "E6") (pin "6") (pinfunction "CLK_6") (pintype "input"))
      (node (ref "E7") (pin "2") (pinfunction "CLK_2") (pintype "input"))
      (node (ref "E7") (pin "6") (pinfunction "CLK_6") (pintype "input"))
      (node (ref "E8") (pin "2") (pinfunction "CLK_2") (pintype "input"))
      (node (ref "E8") (pin "6") (pinfunction "CLK_6") (pintype "input"))
      (node (ref "E9") (pin "2") (pinfunction "CLK_2") (pintype "input"))
      (node (ref "E9") (pin "6") (pinfunction "CLK_6") (pintype "input"))
    )
    (net (code "74") (name "Net-(E12D-O)") (class "Default")
      (node (ref "C2") (pin "1") (pinfunction "1_1") (pintype "passive"))
      (node (ref "E12") (pin "14") (pinfunction "O_14") (pintype "output"))
    )
    (net (code "75") (name "Net-(E13A-I)") (class "Default")
      (node (ref "E13") (pin "14") (pinfunction "I_14") (pintype "input"))
      (node (ref "E17") (pin "8") (pinfunction "~{Q}_8") (pintype "output"))
    )
    (net (code "76") (name "Net-(E13B-I)") (class "Default")
      (node (ref "E13") (pin "13") (pinfunction "I_13") (pintype "input"))
      (node (ref "E17") (pin "9") (pinfunction "Q_9") (pintype "output"))
    )
    (net (code "77") (name "Net-(E13C-O)") (class "Default")
      (node (ref "E13") (pin "3") (pinfunction "O_3") (pintype "output"))
      (node (ref "E17") (pin "7") (pinfunction "K_7") (pintype "input"))
    )
    (net (code "78") (name "Net-(E13D-O)") (class "Default")
      (node (ref "E13") (pin "5") (pinfunction "O_5") (pintype "output"))
      (node (ref "E17") (pin "1") (pinfunction "K_1") (pintype "input"))
      (node (ref "E17") (pin "5") (pinfunction "J_5") (pintype "input"))
      (node (ref "E19") (pin "1") (pinfunction "K_1") (pintype "input"))
    )
    (net (code "79") (name "Net-(E13E-O)") (class "Default")
      (node (ref "E13") (pin "6") (pinfunction "O_6") (pintype "output"))
      (node (ref "E19") (pin "12") (pinfunction "CL_12") (pintype "input"))
    )
    (net (code "80") (name "Net-(E13F-O)") (class "Default")
      (node (ref "E13") (pin "7") (pinfunction "O_7") (pintype "output"))
      (node (ref "E19") (pin "5") (pinfunction "J_5") (pintype "input"))
    )
    (net (code "81") (name "Net-(E14A-I)") (class "Default")
      (node (ref "C19") (pin "2") (pinfunction "2_2") (pintype "passive"))
      (node (ref "E14") (pin "14") (pinfunction "I_14") (pintype "input"))
      (node (ref "R9") (pin "1") (pinfunction "1_1") (pintype "passive"))
    )
    (net (code "82") (name "Net-(E14A-O)") (class "Default")
      (node (ref "E1") (pin "14") (pinfunction "I_14") (pintype "input"))
      (node (ref "E14") (pin "1") (pinfunction "O_1") (pintype "output"))
      (node (ref "E9") (pin "14") (pinfunction "~{Q}_14") (pintype "output"))
    )
    (net (code "83") (name "Net-(E15A-I)") (class "Default")
      (node (ref "E15") (pin "13") (pinfunction "I_13") (pintype "input"))
      (node (ref "R1") (pin "2") (pinfunction "2_2") (pintype "passive"))
      (node (ref "R2") (pin "1") (pinfunction "1_1") (pintype "passive"))
    )
    (net (code "84") (name "Net-(E15A-O)") (class "Default")
      (node (ref "E15") (pin "3") (pinfunction "O_3") (pintype "output"))
      (node (ref "E17") (pin "2") (pinfunction "CLK_2") (pintype "input"))
      (node (ref "E17") (pin "6") (pinfunction "CLK_6") (pintype "input"))
      (node (ref "E18") (pin "2") (pinfunction "CLK_2") (pintype "input"))
      (node (ref "E18") (pin "6") (pinfunction "CLK_6") (pintype "input"))
      (node (ref "E19") (pin "2") (pinfunction "CLK_2") (pintype "input"))
      (node (ref "E19") (pin "6") (pinfunction "CLK_6") (pintype "input"))
    )
    (net (code "85") (name "Net-(E15B-I)") (class "Default")
      (node (ref "E15") (pin "6") (pinfunction "I_6") (pintype "input"))
      (node (ref "R13") (pin "1") (pinfunction "1_1") (pintype "passive"))
      (node (ref "R14") (pin "1") (pinfunction "1_1") (pintype "passive"))
    )
    (net (code "86") (name "Net-(E16A-I)") (class "Default")
      (node (ref "E16") (pin "13") (pinfunction "I_13") (pintype "input"))
      (node (ref "R3") (pin "2") (pinfunction "2_2") (pintype "passive"))
      (node (ref "R4") (pin "1") (pinfunction "1_1") (pintype "passive"))
    )
    (net (code "87") (name "Net-(E16B-I)") (class "Default")
      (node (ref "C2") (pin "2") (pinfunction "2_2") (pintype "passive"))
      (node (ref "E16") (pin "6") (pinfunction "I_6") (pintype "input"))
      (node (ref "R10") (pin "1") (pinfunction "1_1") (pintype "passive"))
    )
    (net (code "88") (name "Net-(E18A-K)") (class "Default")
      (node (ref "E18") (pin "1") (pinfunction "K_1") (pintype "input"))
      (node (ref "E18") (pin "8") (pinfunction "~{Q}_8") (pintype "output"))
    )
    (net (code "89") (name "Net-(E18A-Q)") (class "Default")
      (node (ref "E18") (pin "13") (pinfunction "Q_13") (pintype "output"))
      (node (ref "W4") (pin "1") (pinfunction "1_1") (pintype "passive"))
    )
    (net (code "90") (name "Net-(E19A-Q)") (class "Default")
      (node (ref "E1") (pin "13") (pinfunction "I_13") (pintype "input"))
      (node (ref "E19") (pin "13") (pinfunction "Q_13") (pintype "output"))
    )
    (net (code "91") (name "Net-(Q1-B)") (class "Default")
      (node (ref "Q1") (pin "2") (pinfunction "B_2") (pintype "passive"))
      (node (ref "R37") (pin "2") (pinfunction "2_2") (pintype "passive"))
      (node (ref "R38") (pin "2") (pinfunction "2_2") (pintype "passive"))
    )
    (net (code "92") (name "Net-(Q1-C)") (class "Default")
      (node (ref "Q1") (pin "3") (pinfunction "C_3") (pintype "passive"))
      (node (ref "U$2") (pin "AD2") (pinfunction "1_AD2") (pintype "bidirectional"))
    )
    (net (code "93") (name "Net-(Q2-B)") (class "Default")
      (node (ref "Q2") (pin "2") (pinfunction "B_2") (pintype "passive"))
      (node (ref "R35") (pin "2") (pinfunction "2_2") (pintype "passive"))
      (node (ref "R36") (pin "2") (pinfunction "2_2") (pintype "passive"))
    )
    (net (code "94") (name "Net-(Q2-C)") (class "Default")
      (node (ref "Q2") (pin "3") (pinfunction "C_3") (pintype "passive"))
      (node (ref "U$2") (pin "AL2") (pinfunction "1_AL2") (pintype "bidirectional"))
    )
    (net (code "95") (name "Net-(Q3-B)") (class "Default")
      (node (ref "Q3") (pin "2") (pinfunction "B_2") (pintype "passive"))
      (node (ref "R33") (pin "2") (pinfunction "2_2") (pintype "passive"))
      (node (ref "R34") (pin "1") (pinfunction "1_1") (pintype "passive"))
    )
    (net (code "96") (name "Net-(Q3-C)") (class "Default")
      (node (ref "Q3") (pin "3") (pinfunction "C_3") (pintype "passive"))
      (node (ref "U$2") (pin "AH2") (pinfunction "1_AH2") (pintype "bidirectional"))
    )
    (net (code "97") (name "Net-(Q4-B)") (class "Default")
      (node (ref "Q4") (pin "2") (pinfunction "B_2") (pintype "passive"))
      (node (ref "R7") (pin "2") (pinfunction "2_2") (pintype "passive"))
      (node (ref "R8") (pin "1") (pinfunction "1_1") (pintype "passive"))
    )
    (net (code "98") (name "Net-(Q4-C)") (class "Default")
      (node (ref "Q4") (pin "3") (pinfunction "C_3") (pintype "passive"))
      (node (ref "U$2") (pin "AP2") (pinfunction "1_AP2") (pintype "bidirectional"))
    )
    (net (code "99") (name "Net-(U$2AF-1)") (class "Default")
      (node (ref "R31") (pin "2") (pinfunction "2_2") (pintype "passive"))
      (node (ref "U$2") (pin "AT2") (pinfunction "1_AT2") (pintype "bidirectional"))
    )
    (net (code "100") (name "Net-(U$2AJ-1)") (class "Default")
      (node (ref "R11") (pin "1") (pinfunction "1_1") (pintype "passive"))
      (node (ref "U$2") (pin "AV2") (pinfunction "1_AV2") (pintype "bidirectional"))
    )
    (net (code "101") (name "Net-(U$2AT-1)") (class "Default")
      (node (ref "R13") (pin "2") (pinfunction "2_2") (pintype "passive"))
      (node (ref "U$2") (pin "BE2") (pinfunction "1_BE2") (pintype "bidirectional"))
    )
    (net (code "102") (name "Net-(U$2AV-1)") (class "Default")
      (node (ref "R27") (pin "2") (pinfunction "2_2") (pintype "passive"))
      (node (ref "U$2") (pin "BF2") (pinfunction "1_BF2") (pintype "bidirectional"))
    )
    (net (code "103") (name "Net-(U$2AX-1)") (class "Default")
      (node (ref "R25") (pin "2") (pinfunction "2_2") (pintype "passive"))
      (node (ref "U$2") (pin "BH2") (pinfunction "1_BH2") (pintype "bidirectional"))
    )
    (net (code "104") (name "Net-(U$2AZ-1)") (class "Default")
      (node (ref "R7") (pin "1") (pinfunction "1_1") (pintype "passive"))
      (node (ref "U$2") (pin "BJ2") (pinfunction "1_BJ2") (pintype "bidirectional"))
    )
    (net (code "105") (name "Net-(U$2BB-1)") (class "Default")
      (node (ref "R23") (pin "2") (pinfunction "2_2") (pintype "passive"))
      (node (ref "U$2") (pin "BK2") (pinfunction "1_BK2") (pintype "bidirectional"))
    )
    (net (code "106") (name "Net-(U$2BD-1)") (class "Default")
      (node (ref "R29") (pin "2") (pinfunction "2_2") (pintype "passive"))
      (node (ref "U$2") (pin "BL2") (pinfunction "1_BL2") (pintype "bidirectional"))
    )
    (net (code "107") (name "Net-(U$2BF-1)") (class "Default")
      (node (ref "R19") (pin "2") (pinfunction "2_2") (pintype "passive"))
      (node (ref "U$2") (pin "BM2") (pinfunction "1_BM2") (pintype "bidirectional"))
    )
    (net (code "108") (name "Net-(U$2BH-1)") (class "Default")
      (node (ref "R17") (pin "2") (pinfunction "2_2") (pintype "passive"))
      (node (ref "U$2") (pin "BN2") (pinfunction "1_BN2") (pintype "bidirectional"))
    )
    (net (code "109") (name "Net-(U$2BJ-1)") (class "Default")
      (node (ref "R21") (pin "2") (pinfunction "2_2") (pintype "passive"))
      (node (ref "U$2") (pin "BP2") (pinfunction "1_BP2") (pintype "bidirectional"))
    )
    (net (code "110") (name "Net-(U$2BN-1)") (class "Default")
      (node (ref "R15") (pin "2") (pinfunction "2_2") (pintype "passive"))
      (node (ref "U$2") (pin "BS2") (pinfunction "1_BS2") (pintype "bidirectional"))
    )
    (net (code "111") (name "VCC") (class "Default")
      (node (ref "E19") (pin "3") (pinfunction "J_3") (pintype "input"))
      (node (ref "E5") (pin "5") (pinfunction "J_5") (pintype "input"))
      (node (ref "R10") (pin "2") (pinfunction "2_2") (pintype "passive"))
      (node (ref "R12") (pin "2") (pinfunction "2_2") (pintype "passive"))
      (node (ref "R14") (pin "2") (pinfunction "2_2") (pintype "passive"))
      (node (ref "R16") (pin "2") (pinfunction "2_2") (pintype "passive"))
      (node (ref "R18") (pin "2") (pinfunction "2_2") (pintype "passive"))
      (node (ref "R2") (pin "2") (pinfunction "2_2") (pintype "passive"))
      (node (ref "R20") (pin "2") (pinfunction "2_2") (pintype "passive"))
      (node (ref "R22") (pin "2") (pinfunction "2_2") (pintype "passive"))
      (node (ref "R24") (pin "2") (pinfunction "2_2") (pintype "passive"))
      (node (ref "R26") (pin "2") (pinfunction "2_2") (pintype "passive"))
      (node (ref "R28") (pin "2") (pinfunction "2_2") (pintype "passive"))
      (node (ref "R30") (pin "2") (pinfunction "2_2") (pintype "passive"))
      (node (ref "R32") (pin "2") (pinfunction "2_2") (pintype "passive"))
      (node (ref "R4") (pin "2") (pinfunction "2_2") (pintype "passive"))
      (node (ref "R6") (pin "2") (pinfunction "2_2") (pintype "passive"))
      (node (ref "R8") (pin "2") (pinfunction "2_2") (pintype "passive"))
      (node (ref "U$2") (pin "AJ2") (pinfunction "1_AJ2") (pintype "bidirectional"))
      (node (ref "U$2") (pin "BV2") (pinfunction "1_BV2") (pintype "bidirectional"))
    )
    (net (code "112") (name "unconnected-(E9A-Q-Pad13)") (class "Default")
      (node (ref "E9") (pin "13") (pinfunction "Q_13") (pintype "output"))
    )
    (net (code "113") (name "unconnected-(E14E-O-Pad6)") (class "Default")
      (node (ref "E14") (pin "6") (pinfunction "O_6") (pintype "output"))
    )
    (net (code "114") (name "unconnected-(E15A-E-Pad2)") (class "Default")
      (node (ref "E15") (pin "2") (pinfunction "E_2") (pintype "output"))
    )
    (net (code "115") (name "unconnected-(E15A-R-Pad12)") (class "Default")
      (node (ref "E15") (pin "12") (pinfunction "R_12") (pintype "passive"))
    )
    (net (code "116") (name "unconnected-(E15B-E-Pad10)") (class "Default")
      (node (ref "E15") (pin "10") (pinfunction "E_10") (pintype "output"))
    )
    (net (code "117") (name "unconnected-(E15B-R-Pad9)") (class "Default")
      (node (ref "E15") (pin "9") (pinfunction "R_9") (pintype "passive"))
    )
    (net (code "118") (name "unconnected-(E16A-E-Pad2)") (class "Default")
      (node (ref "E16") (pin "2") (pinfunction "E_2") (pintype "output"))
    )
    (net (code "119") (name "unconnected-(E16A-R-Pad12)") (class "Default")
      (node (ref "E16") (pin "12") (pinfunction "R_12") (pintype "passive"))
    )
    (net (code "120") (name "unconnected-(E16B-E-Pad10)") (class "Default")
      (node (ref "E16") (pin "10") (pinfunction "E_10") (pintype "output"))
    )
    (net (code "121") (name "unconnected-(E16B-R-Pad9)") (class "Default")
      (node (ref "E16") (pin "9") (pinfunction "R_9") (pintype "passive"))
    )
    (net (code "122") (name "unconnected-(E17A-~{Q}-Pad14)") (class "Default")
      (node (ref "E17") (pin "14") (pinfunction "~{Q}_14") (pintype "output"))
    )
    (net (code "123") (name "unconnected-(E18A-~{Q}-Pad14)") (class "Default")
      (node (ref "E18") (pin "14") (pinfunction "~{Q}_14") (pintype "output"))
    )
    (net (code "124") (name "unconnected-(E19B-~{Q}-Pad8)") (class "Default")
      (node (ref "E19") (pin "8") (pinfunction "~{Q}_8") (pintype "output"))
    )
    (net (code "125") (name "unconnected-(E20F-O-Pad7)") (class "Default")
      (node (ref "E20") (pin "7") (pinfunction "O_7") (pintype "output"))
    )
  )
)
